# ultrasonic_sensor.net
KiCad netlist of a schematic drawn in Altium Designer
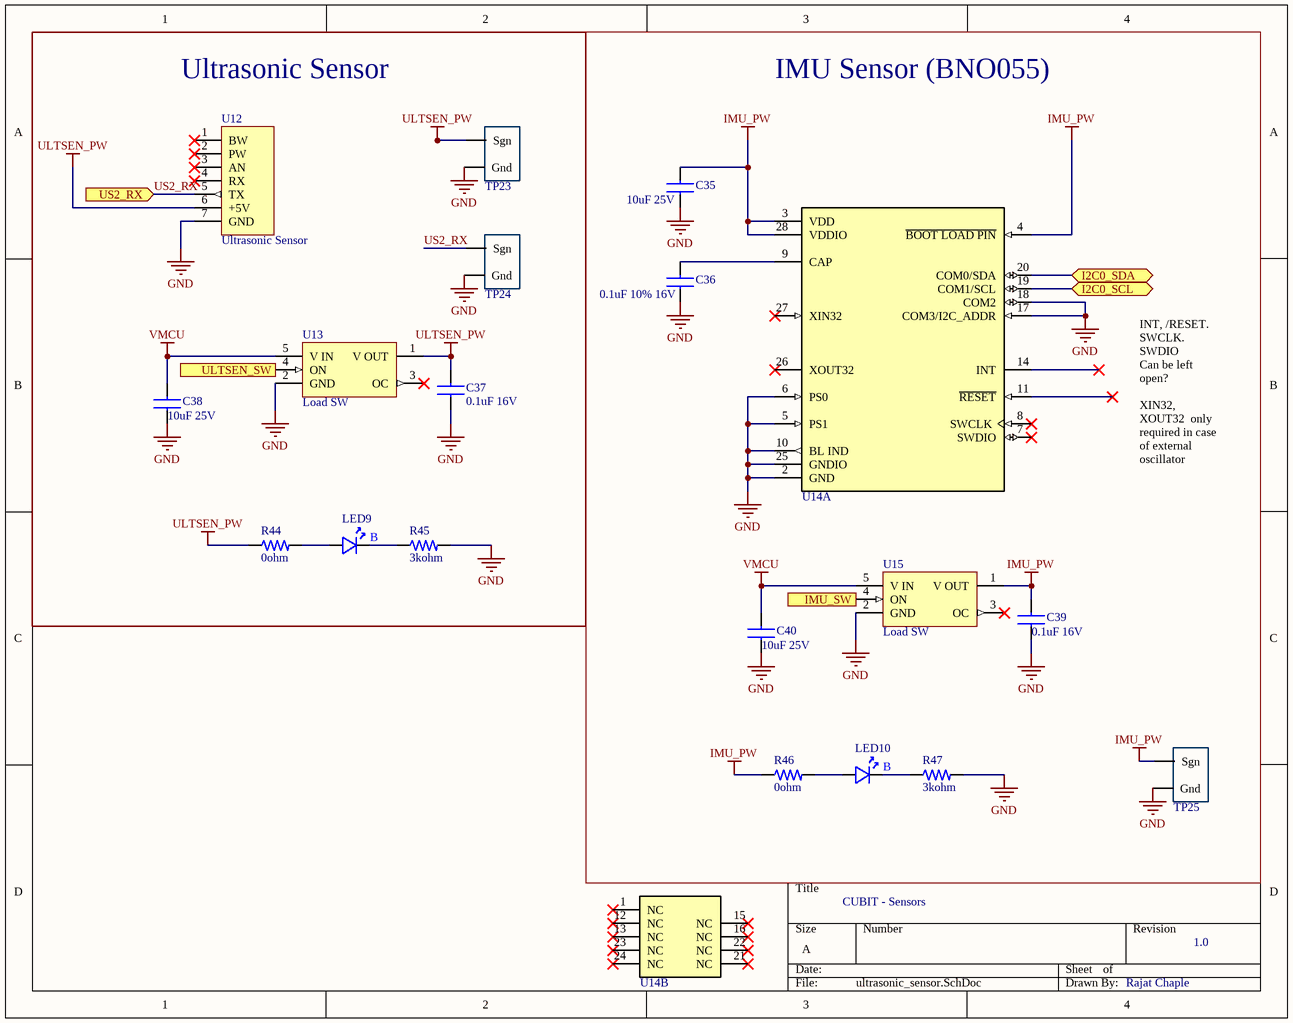
[diagram p0: ultrasonic_sensor.SchDoc]

(export (version "E")
  (design (tool "Eeschema 10.0.6"))
  (components
    (comp (ref "C35")
      (value "10uF 25V")
      (footprint "CAP_0805_02X125")
      (description "Cap 0805 25 V 10 uF ±20% Tolerance X5R Monolithic Ceramic Chip Capacitor")
      (fields
        (field (name "MANUFACTURER") "Murata")
        (field (name "MANUFACTURER PART NUMBER") "GRM21BR61E106KA73K")
      )
      (libsource (lib "LPEDT_proj_lib") (part "GRM21BR61E106KA73K"))
    )
    (comp (ref "C36")
      (value "0.1uF 10% 16V")
      (footprint "CAP_0805_02X125")
      (description "Cap Ceramic 0.1uF 16V X7R 10% SMD 0805 125°C Paper T/R")
      (fields
        (field (name "MANUFACTURER") "KEMET")
        (field (name "MANUFACTURER PART NUMBER") "C0805C104K4RACAUTO")
      )
      (libsource (lib "LPEDT_proj_lib") (part "C0805C104K4RACAUTO"))
    )
    (comp (ref "C37")
      (value "0.1uF 16V")
      (footprint "CAP_0805_02X125")
      (description "Cap Ceramic 0.1uF 16V X7R 10% SMD 0805 125°C Paper T/R")
      (fields
        (field (name "MANUFACTURER") "KEMET")
        (field (name "MANUFACTURER PART NUMBER") "C0805C104K4RACAUTO")
      )
      (libsource (lib "LPEDT_proj_lib") (part "C0805C104K4RACAUTO"))
    )
    (comp (ref "C38")
      (value "10uF 25V")
      (footprint "CAP_0805_02X125")
      (description "Cap 0805 25 V 10 uF ±20% Tolerance X5R Monolithic Ceramic Chip Capacitor")
      (fields
        (field (name "MANUFACTURER") "Murata")
        (field (name "MANUFACTURER PART NUMBER") "GRM21BR61E106KA73K")
      )
      (libsource (lib "LPEDT_proj_lib") (part "GRM21BR61E106KA73K"))
    )
    (comp (ref "C39")
      (value "0.1uF 16V")
      (footprint "CAP_0805_02X125")
      (description "Cap Ceramic 0.1uF 16V X7R 10% SMD 0805 125°C Paper T/R")
      (fields
        (field (name "MANUFACTURER") "KEMET")
        (field (name "MANUFACTURER PART NUMBER") "C0805C104K4RACAUTO")
      )
      (libsource (lib "LPEDT_proj_lib") (part "C0805C104K4RACAUTO"))
    )
    (comp (ref "C40")
      (value "10uF 25V")
      (footprint "CAP_0805_02X125")
      (description "Cap 0805 25 V 10 uF ±20% Tolerance X5R Monolithic Ceramic Chip Capacitor")
      (fields
        (field (name "MANUFACTURER") "Murata")
        (field (name "MANUFACTURER PART NUMBER") "GRM21BR61E106KA73K")
      )
      (libsource (lib "LPEDT_proj_lib") (part "GRM21BR61E106KA73K"))
    )
    (comp (ref "LED9")
      (value "150060BS75000")
      (footprint "LED_0603_RED_WL-SMCW")
      (description "Led, Blue, 470 Nm, 3.2 V, 30 Ma, 145 Mcd Rohs Compliant: Yes")
      (fields (field (name "MANUFACTURER") "Wurth Electronics"))
      (libsource (lib "LPEDT_proj_lib") (part "150060BS75000"))
    )
    (comp (ref "LED10")
      (value "150060BS75000")
      (footprint "LED_0603_RED_WL-SMCW")
      (description "Led, Blue, 470 Nm, 3.2 V, 30 Ma, 145 Mcd Rohs Compliant: Yes")
      (fields (field (name "MANUFACTURER") "Wurth Electronics"))
      (libsource (lib "LPEDT_proj_lib") (part "150060BS75000"))
    )
    (comp (ref "R44")
      (value "0ohm")
      (footprint "CAP_0402_1mm")
      (description "Res 0 Ohms ±5% 0.063 W 0402 Thick Film Surface Mount Chip Resistor")
      (fields
        (field (name "MANUFACTURER") "Samsung")
        (field (name "MANUFACTURER PART NUMBER") "RC1005J000CS")
      )
      (libsource (lib "LPEDT_proj_lib") (part "RC1005J000CS"))
    )
    (comp (ref "R45")
      (value "3kohm")
      (footprint "CAP_0603_1MM")
      (description "Res 3000Ω ± 1.00% 0.1W ± 100ppm/℃ 0603")
      (fields
        (field (name "MANUFACTURER") "Yageo")
        (field (name "MANUFACTURER PART NUMBER") "RC0603FR-073KL")
      )
      (libsource (lib "LPEDT_proj_lib") (part "RC0603FR-073KL"))
    )
    (comp (ref "R46")
      (value "0ohm")
      (footprint "CAP_0402_1mm")
      (description "Res 0 Ohms ±5% 0.063 W 0402 Thick Film Surface Mount Chip Resistor")
      (fields
        (field (name "MANUFACTURER") "Samsung")
        (field (name "MANUFACTURER PART NUMBER") "RC1005J000CS")
      )
      (libsource (lib "LPEDT_proj_lib") (part "RC1005J000CS"))
    )
    (comp (ref "R47")
      (value "3kohm")
      (footprint "CAP_0603_1MM")
      (description "Res 3000Ω ± 1.00% 0.1W ± 100ppm/℃ 0603")
      (fields
        (field (name "MANUFACTURER") "Yageo")
        (field (name "MANUFACTURER PART NUMBER") "RC0603FR-073KL")
      )
      (libsource (lib "LPEDT_proj_lib") (part "RC0603FR-073KL"))
    )
    (comp (ref "TP23")
      (value "10x Probe TP")
      (footprint "TP10x_Probe")
      (description "Test Point 300 mil centers")
      (libsource (lib "LPEDT_proj_lib") (part "TP_10x_Probe"))
    )
    (comp (ref "TP24")
      (value "10x Probe TP")
      (footprint "TP10x_Probe")
      (description "Test Point 300 mil centers")
      (libsource (lib "LPEDT_proj_lib") (part "TP_10x_Probe"))
    )
    (comp (ref "TP25")
      (value "10x Probe TP")
      (footprint "TP10x_Probe")
      (description "Test Point 300 mil centers")
      (libsource (lib "LPEDT_proj_lib") (part "TP_10x_Probe"))
    )
    (comp (ref "U12")
      (value "Ultrasonic Sensor")
      (footprint "7_PIN_100MIL")
      (libsource (lib "LPEDT_proj_lib") (part "Ultrasonic Sensor"))
    )
    (comp (ref "U13")
      (value "Load SW")
      (footprint "SOT65P210X110-5N")
      (description "5.5-V, 0.1-A, 500-mΩ, load switch with current limit and active low enable 5-SC70 -40 to 85")
      (fields
        (field (name "MANUFACTURER") "Texas Instruments")
        (field (name "MANUFACTURER PART NUMBER") "TPS22942DCKR")
      )
      (libsource (lib "LPEDT_proj_lib") (part "TPS22942DCKR"))
    )
    (comp (ref "U14")
      (value "BNO005")
      (footprint "LGA28R50P4X10_380X520X100")
      (libsource (lib "LPEDT_proj_lib") (part "BNO055"))
    )
    (comp (ref "U15")
      (value "Load SW")
      (footprint "SOT65P210X110-5N")
      (description "5.5-V, 0.1-A, 500-mΩ, load switch with current limit and active low enable 5-SC70 -40 to 85")
      (fields
        (field (name "MANUFACTURER") "Texas Instruments")
        (field (name "MANUFACTURER PART NUMBER") "TPS22942DCKR")
      )
      (libsource (lib "LPEDT_proj_lib") (part "TPS22942DCKR"))
    )
  )
  (nets
    (net (code "1") (name "/I2C0_SCL") (class "Default")
      (node (ref "U14") (pin "19") (pinfunction "COM1/SCL_19") (pintype "bidirectional"))
    )
    (net (code "2") (name "/I2C0_SDA") (class "Default")
      (node (ref "U14") (pin "20") (pinfunction "COM0/SDA_20") (pintype "bidirectional"))
    )
    (net (code "3") (name "/IMU_SW") (class "Default")
      (node (ref "U15") (pin "4") (pinfunction "ON_4") (pintype "input"))
    )
    (net (code "4") (name "/ULTSEN_SW") (class "Default")
      (node (ref "U13") (pin "4") (pinfunction "ON_4") (pintype "input"))
    )
    (net (code "5") (name "/US2_RX") (class "Default")
      (node (ref "TP24") (pin "1") (pinfunction "Sgn_1") (pintype "passive"))
      (node (ref "U12") (pin "5") (pinfunction "TX_5") (pintype "output"))
    )
    (net (code "6") (name "GND") (class "Default")
      (node (ref "C35") (pin "2") (pinfunction "2_2") (pintype "passive"))
      (node (ref "C36") (pin "2") (pinfunction "2_2") (pintype "passive"))
      (node (ref "C37") (pin "2") (pinfunction "2_2") (pintype "passive"))
      (node (ref "C38") (pin "2") (pinfunction "2_2") (pintype "passive"))
      (node (ref "C39") (pin "2") (pinfunction "2_2") (pintype "passive"))
      (node (ref "C40") (pin "2") (pinfunction "2_2") (pintype "passive"))
      (node (ref "R45") (pin "2") (pinfunction "2_2") (pintype "passive"))
      (node (ref "R47") (pin "2") (pinfunction "2_2") (pintype "passive"))
      (node (ref "TP23") (pin "2") (pinfunction "Gnd_2") (pintype "passive"))
      (node (ref "TP24") (pin "2") (pinfunction "Gnd_2") (pintype "passive"))
      (node (ref "TP25") (pin "2") (pinfunction "Gnd_2") (pintype "passive"))
      (node (ref "U12") (pin "7") (pinfunction "GND_7") (pintype "power_in"))
      (node (ref "U13") (pin "2") (pinfunction "GND_2") (pintype "power_in"))
      (node (ref "U14") (pin "10") (pinfunction "BL_IND_10") (pintype "output"))
      (node (ref "U14") (pin "17") (pinfunction "COM3/I2C_ADDR_17") (pintype "input"))
      (node (ref "U14") (pin "18") (pinfunction "COM2_18") (pintype "bidirectional"))
      (node (ref "U14") (pin "2") (pinfunction "GND_2") (pintype "power_in"))
      (node (ref "U14") (pin "25") (pinfunction "GNDIO_25") (pintype "power_in"))
      (node (ref "U14") (pin "5") (pinfunction "PS1_5") (pintype "input"))
      (node (ref "U14") (pin "6") (pinfunction "PS0_6") (pintype "input"))
      (node (ref "U15") (pin "2") (pinfunction "GND_2") (pintype "power_in"))
    )
    (net (code "7") (name "IMU_PW") (class "Default")
      (node (ref "C35") (pin "1") (pinfunction "1_1") (pintype "passive"))
      (node (ref "C39") (pin "1") (pinfunction "1_1") (pintype "passive"))
      (node (ref "R46") (pin "1") (pinfunction "1_1") (pintype "passive"))
      (node (ref "TP25") (pin "1") (pinfunction "Sgn_1") (pintype "passive"))
      (node (ref "U14") (pin "28") (pinfunction "VDDIO_28") (pintype "power_in"))
      (node (ref "U14") (pin "3") (pinfunction "VDD_3") (pintype "power_in"))
      (node (ref "U14") (pin "4") (pinfunction "~{BOOT_LOAD_PIN}_4") (pintype "input"))
      (node (ref "U15") (pin "1") (pinfunction "V_OUT_1") (pintype "power_in"))
    )
    (net (code "8") (name "Net-(LED9-PadA)") (class "Default")
      (node (ref "LED9") (pin "A") (pinfunction "A_A") (pintype "passive"))
      (node (ref "R44") (pin "2") (pinfunction "2_2") (pintype "passive"))
    )
    (net (code "9") (name "Net-(LED9-PadC)") (class "Default")
      (node (ref "LED9") (pin "C") (pinfunction "C_C") (pintype "passive"))
      (node (ref "R45") (pin "1") (pinfunction "1_1") (pintype "passive"))
    )
    (net (code "10") (name "Net-(LED10-PadA)") (class "Default")
      (node (ref "LED10") (pin "A") (pinfunction "A_A") (pintype "passive"))
      (node (ref "R46") (pin "2") (pinfunction "2_2") (pintype "passive"))
    )
    (net (code "11") (name "Net-(LED10-PadC)") (class "Default")
      (node (ref "LED10") (pin "C") (pinfunction "C_C") (pintype "passive"))
      (node (ref "R47") (pin "1") (pinfunction "1_1") (pintype "passive"))
    )
    (net (code "12") (name "Net-(U14A-CAP)") (class "Default")
      (node (ref "C36") (pin "1") (pinfunction "1_1") (pintype "passive"))
      (node (ref "U14") (pin "9") (pinfunction "CAP_9") (pintype "passive"))
    )
    (net (code "13") (name "ULTSEN_PW") (class "Default")
      (node (ref "C37") (pin "1") (pinfunction "1_1") (pintype "passive"))
      (node (ref "R44") (pin "1") (pinfunction "1_1") (pintype "passive"))
      (node (ref "TP23") (pin "1") (pinfunction "Sgn_1") (pintype "passive"))
      (node (ref "U12") (pin "6") (pinfunction "+5V_6") (pintype "power_in"))
      (node (ref "U13") (pin "1") (pinfunction "V_OUT_1") (pintype "power_in"))
    )
    (net (code "14") (name "VMCU") (class "Default")
      (node (ref "C38") (pin "1") (pinfunction "1_1") (pintype "passive"))
      (node (ref "C40") (pin "1") (pinfunction "1_1") (pintype "passive"))
      (node (ref "U13") (pin "5") (pinfunction "V_IN_5") (pintype "power_in"))
      (node (ref "U15") (pin "5") (pinfunction "V_IN_5") (pintype "power_in"))
    )
    (net (code "15") (name "unconnected-(U12-AN-Pad3)") (class "Default")
      (node (ref "U12") (pin "3") (pinfunction "AN_3") (pintype "passive+no_connect"))
    )
    (net (code "16") (name "unconnected-(U12-BW-Pad1)") (class "Default")
      (node (ref "U12") (pin "1") (pinfunction "BW_1") (pintype "passive+no_connect"))
    )
    (net (code "17") (name "unconnected-(U12-PW-Pad2)") (class "Default")
      (node (ref "U12") (pin "2") (pinfunction "PW_2") (pintype "passive+no_connect"))
    )
    (net (code "18") (name "unconnected-(U12-RX-Pad4)") (class "Default")
      (node (ref "U12") (pin "4") (pinfunction "RX_4") (pintype "passive+no_connect"))
    )
    (net (code "19") (name "unconnected-(U13-OC-Pad3)") (class "Default")
      (node (ref "U13") (pin "3") (pinfunction "OC_3") (pintype "output+no_connect"))
    )
    (net (code "20") (name "unconnected-(U14A-INT-Pad14)") (class "Default")
      (node (ref "U14") (pin "14") (pinfunction "INT_14") (pintype "passive+no_connect"))
    )
    (net (code "21") (name "unconnected-(U14A-SWCLK-Pad8)") (class "Default")
      (node (ref "U14") (pin "8") (pinfunction "SWCLK_8") (pintype "input+no_connect"))
    )
    (net (code "22") (name "unconnected-(U14A-SWDIO-Pad7)") (class "Default")
      (node (ref "U14") (pin "7") (pinfunction "SWDIO_7") (pintype "bidirectional+no_connect"))
    )
    (net (code "23") (name "unconnected-(U14A-XIN32-Pad27)") (class "Default")
      (node (ref "U14") (pin "27") (pinfunction "XIN32_27") (pintype "input+no_connect"))
    )
    (net (code "24") (name "unconnected-(U14A-XOUT32-Pad26)") (class "Default")
      (node (ref "U14") (pin "26") (pinfunction "XOUT32_26") (pintype "passive+no_connect"))
    )
    (net (code "25") (name "unconnected-(U14A-~{RESET}-Pad11)") (class "Default")
      (node (ref "U14") (pin "11") (pinfunction "~{RESET}_11") (pintype "input+no_connect"))
    )
    (net (code "26") (name "unconnected-(U14B-NC-Pad1)") (class "Default")
      (node (ref "U14") (pin "1") (pinfunction "NC_1") (pintype "passive+no_connect"))
    )
    (net (code "27") (name "unconnected-(U14B-NC-Pad12)") (class "Default")
      (node (ref "U14") (pin "12") (pinfunction "NC_12") (pintype "passive+no_connect"))
    )
    (net (code "28") (name "unconnected-(U14B-NC-Pad13)") (class "Default")
      (node (ref "U14") (pin "13") (pinfunction "NC_13") (pintype "passive+no_connect"))
    )
    (net (code "29") (name "unconnected-(U14B-NC-Pad15)") (class "Default")
      (node (ref "U14") (pin "15") (pinfunction "NC_15") (pintype "passive+no_connect"))
    )
    (net (code "30") (name "unconnected-(U14B-NC-Pad16)") (class "Default")
      (node (ref "U14") (pin "16") (pinfunction "NC_16") (pintype "passive+no_connect"))
    )
    (net (code "31") (name "unconnected-(U14B-NC-Pad21)") (class "Default")
      (node (ref "U14") (pin "21") (pinfunction "NC_21") (pintype "passive+no_connect"))
    )
    (net (code "32") (name "unconnected-(U14B-NC-Pad22)") (class "Default")
      (node (ref "U14") (pin "22") (pinfunction "NC_22") (pintype "passive+no_connect"))
    )
    (net (code "33") (name "unconnected-(U14B-NC-Pad23)") (class "Default")
      (node (ref "U14") (pin "23") (pinfunction "NC_23") (pintype "passive+no_connect"))
    )
    (net (code "34") (name "unconnected-(U14B-NC-Pad24)") (class "Default")
      (node (ref "U14") (pin "24") (pinfunction "NC_24") (pintype "passive+no_connect"))
    )
    (net (code "35") (name "unconnected-(U15-OC-Pad3)") (class "Default")
      (node (ref "U15") (pin "3") (pinfunction "OC_3") (pintype "output+no_connect"))
    )
  )
)
